# Sheet1.net
KiCad netlist of a schematic drawn in Altium Designer
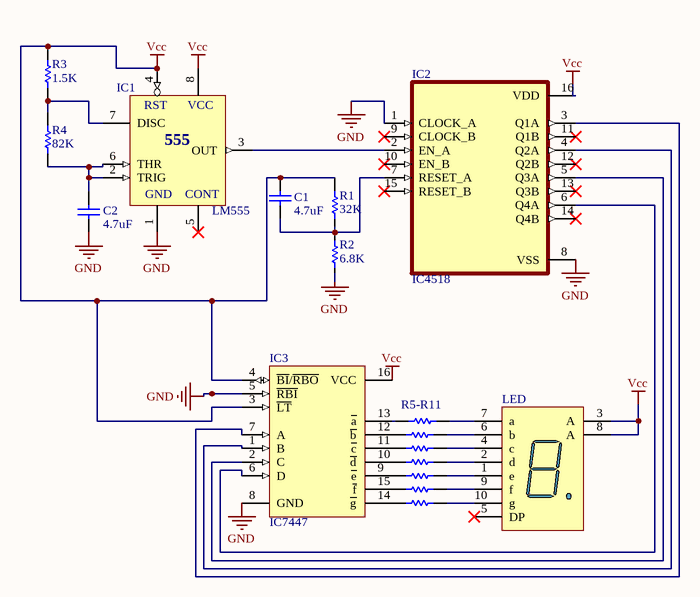
[diagram p0: Sheet1.SchDoc]

(export (version "E")
  (design (tool "Eeschema 10.0.6"))
  (components
    (comp (ref "C1")
      (value "4.7uF")
      (footprint "C3MM")
      (description "Capacitor")
      (fields (field (name "Comment") "Cap") (field (name "PUBLISHER") "Altium Limited"))
      (libsource (lib "Schematic") (part "Cap"))
    )
    (comp (ref "C2")
      (value "4.7uF")
      (footprint "C3MM")
      (description "Capacitor")
      (fields (field (name "Comment") "Cap") (field (name "PUBLISHER") "Altium Limited"))
      (libsource (lib "Schematic") (part "Cap"))
    )
    (comp (ref "IC1")
      (value "LM555")
      (footprint "DIP8")
      (description "Timer")
      (libsource (lib "Cty1") (part "LM555"))
    )
    (comp (ref "IC2")
      (value "IC4518")
      (footprint "DIP794W45P254L1969H508Q16")
      (description "CMOS Dual BCD Up-Counter 16-PDIP -55 to 125")
      (fields (field (name "MP") "CD4518BE") (field (name "MF") "Texas Instruments"))
      (libsource (lib "CD4518") (part "CD4518BE"))
    )
    (comp (ref "IC3")
      (value "IC7447")
      (footprint "DIP16/W0.3")
      (description "BCD to 7-Segment Decoder/Driver")
      (libsource (lib "syhaunguyen") (part "7447"))
    )
    (comp (ref "LED")
      (value "7SEG-A")
      (footprint "LED7SEG")
      (description "14.2 mm General Purpose Blue 7-Segment Display: CA, RH DP, Gray Surface")
      (fields (field (name "PUBLISHER") "Altium Limited"))
      (libsource (lib "Cty1") (part "LED7SEG-A"))
    )
    (comp (ref "R1")
      (value "32K")
      (footprint "Res 0805 SMD")
      (description "RES SMD 249K OHM 1% 1/10W 0805")
      (fields
        (field (name "MANUFACTURER") "Yageo")
        (field (name "MANUFACTURER PART NUMBER") "RC0603FR-07249KL")
      )
      (libsource (lib "SCH_MyLib_0") (part "RES-0805"))
    )
    (comp (ref "R2")
      (value "6.8K")
      (footprint "Res 0805 SMD")
      (description "RES SMD 249K OHM 1% 1/10W 0805")
      (fields
        (field (name "MANUFACTURER") "Yageo")
        (field (name "MANUFACTURER PART NUMBER") "RC0603FR-07249KL")
      )
      (libsource (lib "SCH_MyLib_0") (part "RES-0805"))
    )
    (comp (ref "R3")
      (value "1.5K")
      (footprint "Res 0805 SMD")
      (description "RES SMD 249K OHM 1% 1/10W 0805")
      (fields
        (field (name "MANUFACTURER") "Yageo")
        (field (name "MANUFACTURER PART NUMBER") "RC0603FR-07249KL")
      )
      (libsource (lib "SCH_MyLib_0") (part "RES-0805"))
    )
    (comp (ref "R4")
      (value "82K")
      (footprint "Res 0805 SMD")
      (description "RES SMD 249K OHM 1% 1/10W 0805")
      (fields
        (field (name "MANUFACTURER") "Yageo")
        (field (name "MANUFACTURER PART NUMBER") "RC0603FR-07249KL")
      )
      (libsource (lib "SCH_MyLib_0") (part "RES-0805"))
    )
    (comp (ref "R5")
      (value "470")
      (footprint "Res 0805 SMD")
      (description "RES SMD 249K OHM 1% 1/10W 0805")
      (fields
        (field (name "MANUFACTURER") "Yageo")
        (field (name "MANUFACTURER PART NUMBER") "RC0603FR-07249KL")
      )
      (libsource (lib "SCH_MyLib_0") (part "RES-0805"))
    )
    (comp (ref "R6")
      (value "470")
      (footprint "Res 0805 SMD")
      (description "RES SMD 249K OHM 1% 1/10W 0805")
      (fields
        (field (name "MANUFACTURER") "Yageo")
        (field (name "MANUFACTURER PART NUMBER") "RC0603FR-07249KL")
      )
      (libsource (lib "SCH_MyLib_0") (part "RES-0805"))
    )
    (comp (ref "R7")
      (value "470")
      (footprint "Res 0805 SMD")
      (description "RES SMD 249K OHM 1% 1/10W 0805")
      (fields
        (field (name "MANUFACTURER") "Yageo")
        (field (name "MANUFACTURER PART NUMBER") "RC0603FR-07249KL")
      )
      (libsource (lib "SCH_MyLib_0") (part "RES-0805"))
    )
    (comp (ref "R8")
      (value "470")
      (footprint "Res 0805 SMD")
      (description "RES SMD 249K OHM 1% 1/10W 0805")
      (fields
        (field (name "MANUFACTURER") "Yageo")
        (field (name "MANUFACTURER PART NUMBER") "RC0603FR-07249KL")
      )
      (libsource (lib "SCH_MyLib_0") (part "RES-0805"))
    )
    (comp (ref "R9")
      (value "470")
      (footprint "Res 0805 SMD")
      (description "RES SMD 249K OHM 1% 1/10W 0805")
      (fields
        (field (name "MANUFACTURER") "Yageo")
        (field (name "MANUFACTURER PART NUMBER") "RC0603FR-07249KL")
      )
      (libsource (lib "SCH_MyLib_0") (part "RES-0805"))
    )
    (comp (ref "R10")
      (value "470")
      (footprint "Res 0805 SMD")
      (description "RES SMD 249K OHM 1% 1/10W 0805")
      (fields
        (field (name "MANUFACTURER") "Yageo")
        (field (name "MANUFACTURER PART NUMBER") "RC0603FR-07249KL")
      )
      (libsource (lib "SCH_MyLib_0") (part "RES-0805"))
    )
    (comp (ref "R11")
      (value "470")
      (footprint "Res 0805 SMD")
      (description "RES SMD 249K OHM 1% 1/10W 0805")
      (fields
        (field (name "MANUFACTURER") "Yageo")
        (field (name "MANUFACTURER PART NUMBER") "RC0603FR-07249KL")
      )
      (libsource (lib "SCH_MyLib_0") (part "RES-0805"))
    )
  )
  (nets
    (net (code "1") (name "GND") (class "Default")
      (node (ref "C2") (pin "1") (pinfunction "1_1") (pintype "passive"))
      (node (ref "IC1") (pin "1") (pinfunction "GND_1") (pintype "power_in"))
      (node (ref "IC2") (pin "1") (pinfunction "CLOCK_A_1") (pintype "input"))
      (node (ref "IC2") (pin "8") (pinfunction "VSS_8") (pintype "power_in"))
      (node (ref "IC3") (pin "5") (pinfunction "~{RBI}_5") (pintype "input"))
      (node (ref "IC3") (pin "8") (pinfunction "GND_8") (pintype "power_in"))
      (node (ref "R2") (pin "1") (pinfunction "1_1") (pintype "passive"))
    )
    (net (code "2") (name "Net-(IC1-DISC)") (class "Default")
      (node (ref "IC1") (pin "7") (pinfunction "DISC_7") (pintype "open_collector"))
      (node (ref "R3") (pin "1") (pinfunction "1_1") (pintype "passive"))
      (node (ref "R4") (pin "2") (pinfunction "2_2") (pintype "passive"))
    )
    (net (code "3") (name "Net-(IC1-OUT)") (class "Default")
      (node (ref "IC1") (pin "3") (pinfunction "OUT_3") (pintype "output"))
      (node (ref "IC2") (pin "2") (pinfunction "EN_A_2") (pintype "input"))
    )
    (net (code "4") (name "Net-(IC1-THR)") (class "Default")
      (node (ref "C2") (pin "2") (pinfunction "2_2") (pintype "passive"))
      (node (ref "IC1") (pin "2") (pinfunction "TRIG_2") (pintype "input"))
      (node (ref "IC1") (pin "6") (pinfunction "THR_6") (pintype "input"))
      (node (ref "R4") (pin "1") (pinfunction "1_1") (pintype "passive"))
    )
    (net (code "5") (name "Net-(IC2-Q1A)") (class "Default")
      (node (ref "IC2") (pin "3") (pinfunction "Q1A_3") (pintype "output"))
      (node (ref "IC3") (pin "7") (pinfunction "A_7") (pintype "input"))
    )
    (net (code "6") (name "Net-(IC2-Q2A)") (class "Default")
      (node (ref "IC2") (pin "4") (pinfunction "Q2A_4") (pintype "output"))
      (node (ref "IC3") (pin "1") (pinfunction "B_1") (pintype "input"))
    )
    (net (code "7") (name "Net-(IC2-Q3A)") (class "Default")
      (node (ref "IC2") (pin "5") (pinfunction "Q3A_5") (pintype "output"))
      (node (ref "IC3") (pin "2") (pinfunction "C_2") (pintype "input"))
    )
    (net (code "8") (name "Net-(IC2-Q4A)") (class "Default")
      (node (ref "IC2") (pin "6") (pinfunction "Q4A_6") (pintype "output"))
      (node (ref "IC3") (pin "6") (pinfunction "D_6") (pintype "input"))
    )
    (net (code "9") (name "Net-(IC2-RESET_A)") (class "Default")
      (node (ref "C1") (pin "1") (pinfunction "1_1") (pintype "passive"))
      (node (ref "IC2") (pin "7") (pinfunction "RESET_A_7") (pintype "input"))
      (node (ref "R1") (pin "1") (pinfunction "1_1") (pintype "passive"))
      (node (ref "R2") (pin "2") (pinfunction "2_2") (pintype "passive"))
    )
    (net (code "10") (name "Net-(IC3-~{a})") (class "Default")
      (node (ref "IC3") (pin "13") (pinfunction "~{a}_13") (pintype "open_collector"))
      (node (ref "R5") (pin "2") (pinfunction "2_2") (pintype "passive"))
    )
    (net (code "11") (name "Net-(IC3-~{b})") (class "Default")
      (node (ref "IC3") (pin "12") (pinfunction "~{b}_12") (pintype "open_collector"))
      (node (ref "R6") (pin "1") (pinfunction "1_1") (pintype "passive"))
    )
    (net (code "12") (name "Net-(IC3-~{c})") (class "Default")
      (node (ref "IC3") (pin "11") (pinfunction "~{c}_11") (pintype "open_collector"))
      (node (ref "R7") (pin "1") (pinfunction "1_1") (pintype "passive"))
    )
    (net (code "13") (name "Net-(IC3-~{d})") (class "Default")
      (node (ref "IC3") (pin "10") (pinfunction "~{d}_10") (pintype "open_collector"))
      (node (ref "R8") (pin "1") (pinfunction "1_1") (pintype "passive"))
    )
    (net (code "14") (name "Net-(IC3-~{e})") (class "Default")
      (node (ref "IC3") (pin "9") (pinfunction "~{e}_9") (pintype "open_collector"))
      (node (ref "R9") (pin "1") (pinfunction "1_1") (pintype "passive"))
    )
    (net (code "15") (name "Net-(IC3-~{f})") (class "Default")
      (node (ref "IC3") (pin "15") (pinfunction "~{f}_15") (pintype "open_collector"))
      (node (ref "R10") (pin "1") (pinfunction "1_1") (pintype "passive"))
    )
    (net (code "16") (name "Net-(IC3-~{g})") (class "Default")
      (node (ref "IC3") (pin "14") (pinfunction "~{g}_14") (pintype "open_collector"))
      (node (ref "R11") (pin "1") (pinfunction "1_1") (pintype "passive"))
    )
    (net (code "17") (name "Net-(LED-a)") (class "Default")
      (node (ref "LED") (pin "7") (pinfunction "a_7") (pintype "passive"))
      (node (ref "R5") (pin "1") (pinfunction "1_1") (pintype "passive"))
    )
    (net (code "18") (name "Net-(LED-b)") (class "Default")
      (node (ref "LED") (pin "6") (pinfunction "b_6") (pintype "passive"))
      (node (ref "R6") (pin "2") (pinfunction "2_2") (pintype "passive"))
    )
    (net (code "19") (name "Net-(LED-c)") (class "Default")
      (node (ref "LED") (pin "4") (pinfunction "c_4") (pintype "passive"))
      (node (ref "R7") (pin "2") (pinfunction "2_2") (pintype "passive"))
    )
    (net (code "20") (name "Net-(LED-d)") (class "Default")
      (node (ref "LED") (pin "2") (pinfunction "d_2") (pintype "passive"))
      (node (ref "R8") (pin "2") (pinfunction "2_2") (pintype "passive"))
    )
    (net (code "21") (name "Net-(LED-e)") (class "Default")
      (node (ref "LED") (pin "1") (pinfunction "e_1") (pintype "passive"))
      (node (ref "R9") (pin "2") (pinfunction "2_2") (pintype "passive"))
    )
    (net (code "22") (name "Net-(LED-f)") (class "Default")
      (node (ref "LED") (pin "9") (pinfunction "f_9") (pintype "passive"))
      (node (ref "R10") (pin "2") (pinfunction "2_2") (pintype "passive"))
    )
    (net (code "23") (name "Net-(LED-g)") (class "Default")
      (node (ref "LED") (pin "10") (pinfunction "g_10") (pintype "passive"))
      (node (ref "R11") (pin "2") (pinfunction "2_2") (pintype "passive"))
    )
    (net (code "24") (name "Vcc") (class "Default")
      (node (ref "C1") (pin "2") (pinfunction "2_2") (pintype "passive"))
      (node (ref "IC1") (pin "4") (pinfunction "RST_4") (pintype "input"))
      (node (ref "IC1") (pin "8") (pinfunction "VCC_8") (pintype "power_in"))
      (node (ref "IC2") (pin "16") (pinfunction "VDD_16") (pintype "power_in"))
      (node (ref "IC3") (pin "16") (pinfunction "VCC_16") (pintype "power_in"))
      (node (ref "IC3") (pin "3") (pinfunction "~{LT}_3") (pintype "input"))
      (node (ref "IC3") (pin "4") (pinfunction "~{BI}/~{RBO}_4") (pintype "bidirectional"))
      (node (ref "LED") (pin "3") (pinfunction "A_3") (pintype "passive"))
      (node (ref "LED") (pin "8") (pinfunction "A_8") (pintype "passive"))
      (node (ref "R1") (pin "2") (pinfunction "2_2") (pintype "passive"))
      (node (ref "R3") (pin "2") (pinfunction "2_2") (pintype "passive"))
    )
    (net (code "25") (name "unconnected-(IC1-CONT-Pad5)") (class "Default")
      (node (ref "IC1") (pin "5") (pinfunction "CONT_5") (pintype "passive+no_connect"))
    )
    (net (code "26") (name "unconnected-(IC2-CLOCK_B-Pad9)") (class "Default")
      (node (ref "IC2") (pin "9") (pinfunction "CLOCK_B_9") (pintype "input+no_connect"))
    )
    (net (code "27") (name "unconnected-(IC2-EN_B-Pad10)") (class "Default")
      (node (ref "IC2") (pin "10") (pinfunction "EN_B_10") (pintype "input+no_connect"))
    )
    (net (code "28") (name "unconnected-(IC2-Q1B-Pad11)") (class "Default")
      (node (ref "IC2") (pin "11") (pinfunction "Q1B_11") (pintype "output+no_connect"))
    )
    (net (code "29") (name "unconnected-(IC2-Q2B-Pad12)") (class "Default")
      (node (ref "IC2") (pin "12") (pinfunction "Q2B_12") (pintype "output+no_connect"))
    )
    (net (code "30") (name "unconnected-(IC2-Q3B-Pad13)") (class "Default")
      (node (ref "IC2") (pin "13") (pinfunction "Q3B_13") (pintype "output+no_connect"))
    )
    (net (code "31") (name "unconnected-(IC2-Q4B-Pad14)") (class "Default")
      (node (ref "IC2") (pin "14") (pinfunction "Q4B_14") (pintype "output+no_connect"))
    )
    (net (code "32") (name "unconnected-(IC2-RESET_B-Pad15)") (class "Default")
      (node (ref "IC2") (pin "15") (pinfunction "RESET_B_15") (pintype "input+no_connect"))
    )
    (net (code "33") (name "unconnected-(LED-DP-Pad5)") (class "Default")
      (node (ref "LED") (pin "5") (pinfunction "DP_5") (pintype "passive+no_connect"))
    )
  )
)
